# Display_Schematic.net
KiCad netlist of a schematic drawn in Altium Designer
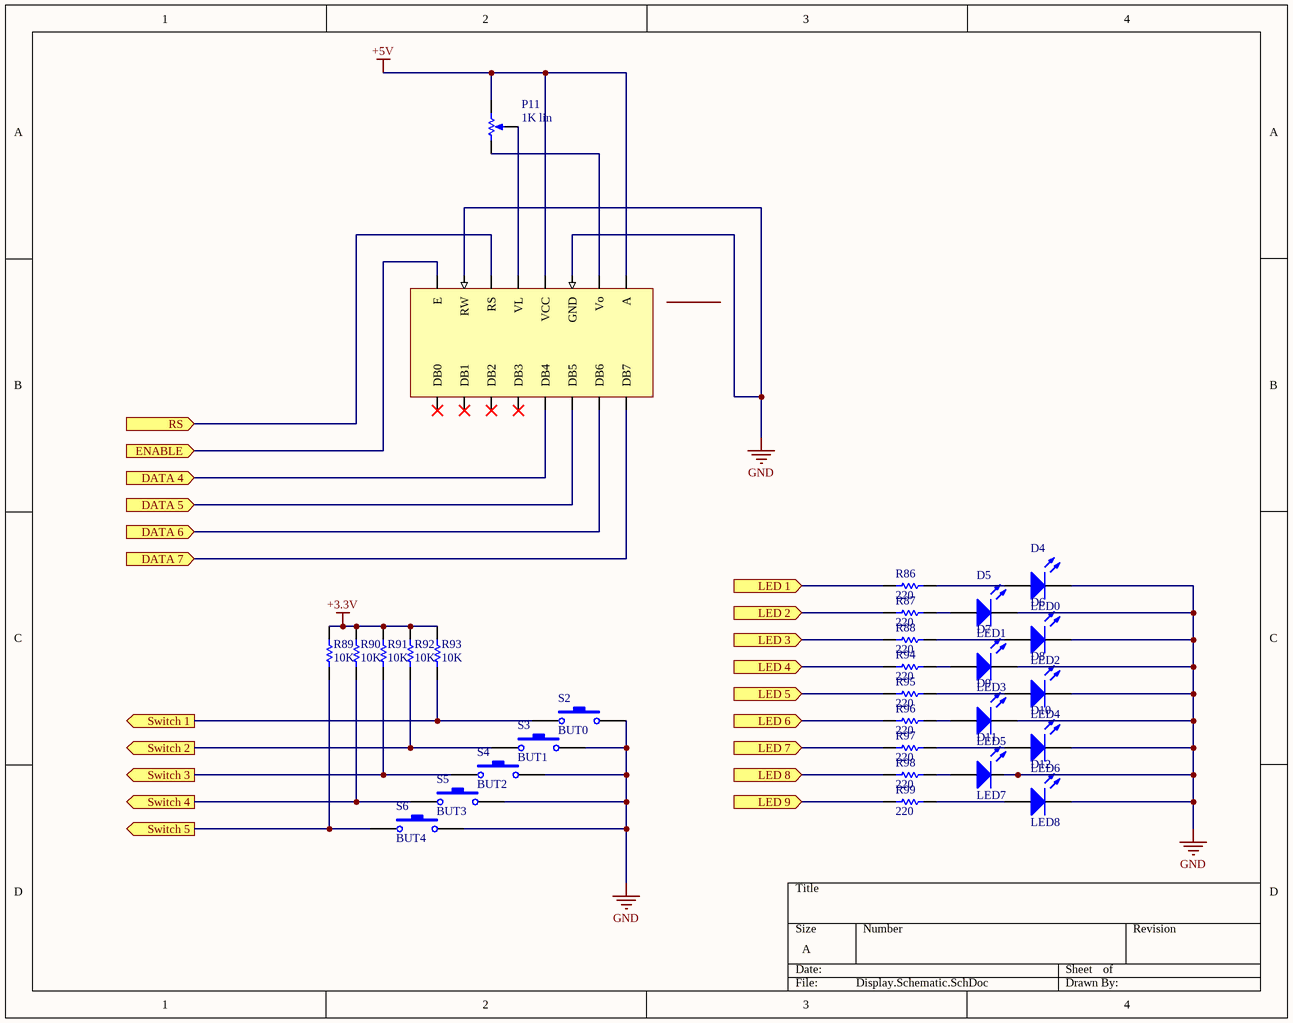
[diagram p0: Display.Schematic.SchDoc]

(export (version "E")
  (design (tool "Eeschema 10.0.6"))
  (components
    (comp (ref "D4")
      (value "LED0")
      (footprint "LED-0")
      (description "Typical INFRARED GaAs LED")
      (fields (field (name "PUBLISHER") "Altium Limited"))
      (libsource (lib "Miscellaneous Devices") (part "LED0"))
    )
    (comp (ref "D5")
      (value "LED1")
      (footprint "LED-0")
      (description "Typical INFRARED GaAs LED")
      (fields (field (name "PUBLISHER") "Altium Limited"))
      (libsource (lib "Miscellaneous Devices") (part "LED0"))
    )
    (comp (ref "D6")
      (value "LED2")
      (footprint "LED-0")
      (description "Typical INFRARED GaAs LED")
      (fields (field (name "PUBLISHER") "Altium Limited"))
      (libsource (lib "Miscellaneous Devices") (part "LED0"))
    )
    (comp (ref "D7")
      (value "LED3")
      (footprint "LED-0")
      (description "Typical INFRARED GaAs LED")
      (fields (field (name "PUBLISHER") "Altium Limited"))
      (libsource (lib "Miscellaneous Devices") (part "LED0"))
    )
    (comp (ref "D8")
      (value "LED4")
      (footprint "LED-0")
      (description "Typical INFRARED GaAs LED")
      (fields (field (name "PUBLISHER") "Altium Limited"))
      (libsource (lib "Miscellaneous Devices") (part "LED0"))
    )
    (comp (ref "D9")
      (value "LED5")
      (footprint "LED-0")
      (description "Typical INFRARED GaAs LED")
      (fields (field (name "PUBLISHER") "Altium Limited"))
      (libsource (lib "Miscellaneous Devices") (part "LED0"))
    )
    (comp (ref "D10")
      (value "LED6")
      (footprint "LED-0")
      (description "Typical INFRARED GaAs LED")
      (fields (field (name "PUBLISHER") "Altium Limited"))
      (libsource (lib "Miscellaneous Devices") (part "LED0"))
    )
    (comp (ref "D11")
      (value "LED7")
      (footprint "LED-0")
      (description "Typical INFRARED GaAs LED")
      (fields (field (name "PUBLISHER") "Altium Limited"))
      (libsource (lib "Miscellaneous Devices") (part "LED0"))
    )
    (comp (ref "D12")
      (value "LED8")
      (footprint "LED-0")
      (description "Typical INFRARED GaAs LED")
      (fields (field (name "PUBLISHER") "Altium Limited"))
      (libsource (lib "Miscellaneous Devices") (part "LED0"))
    )
    (comp (ref "Display")
      (value "16x2 LCD")
      (footprint "Display")
      (libsource (lib "display") (part "Display"))
    )
    (comp (ref "P11")
      (value "1K lin")
      (footprint "VR5")
      (description "Potentiometer")
      (fields (field (name "PUBLISHER") "Altium Limited"))
      (libsource (lib "Miscellaneous Devices") (part "RPot"))
    )
    (comp (ref "R86")
      (value "220")
      (footprint "CAPC1608N")
      (description "Resistor")
      (fields (field (name "PUBLISHER") "Altium Limited"))
      (libsource (lib "Miscellaneous Devices") (part "Res1"))
    )
    (comp (ref "R87")
      (value "220")
      (footprint "CAPC1608N")
      (description "Resistor")
      (fields (field (name "PUBLISHER") "Altium Limited"))
      (libsource (lib "Miscellaneous Devices") (part "Res1"))
    )
    (comp (ref "R88")
      (value "220")
      (footprint "CAPC1608N")
      (description "Resistor")
      (fields (field (name "PUBLISHER") "Altium Limited"))
      (libsource (lib "Miscellaneous Devices") (part "Res1"))
    )
    (comp (ref "R89")
      (value "10K")
      (footprint "CAPC1608N")
      (description "Resistor")
      (fields (field (name "PUBLISHER") "Altium Limited"))
      (libsource (lib "Miscellaneous Devices") (part "Res1"))
    )
    (comp (ref "R90")
      (value "10K")
      (footprint "CAPC1608N")
      (description "Resistor")
      (fields (field (name "PUBLISHER") "Altium Limited"))
      (libsource (lib "Miscellaneous Devices") (part "Res1"))
    )
    (comp (ref "R91")
      (value "10K")
      (footprint "CAPC1608N")
      (description "Resistor")
      (fields (field (name "PUBLISHER") "Altium Limited"))
      (libsource (lib "Miscellaneous Devices") (part "Res1"))
    )
    (comp (ref "R92")
      (value "10K")
      (footprint "CAPC1608N")
      (description "Resistor")
      (fields (field (name "PUBLISHER") "Altium Limited"))
      (libsource (lib "Miscellaneous Devices") (part "Res1"))
    )
    (comp (ref "R93")
      (value "10K")
      (footprint "CAPC1608N")
      (description "Resistor")
      (fields (field (name "PUBLISHER") "Altium Limited"))
      (libsource (lib "Miscellaneous Devices") (part "Res1"))
    )
    (comp (ref "R94")
      (value "220")
      (footprint "CAPC1608N")
      (description "Resistor")
      (fields (field (name "PUBLISHER") "Altium Limited"))
      (libsource (lib "Miscellaneous Devices") (part "Res1"))
    )
    (comp (ref "R95")
      (value "220")
      (footprint "CAPC1608N")
      (description "Resistor")
      (fields (field (name "PUBLISHER") "Altium Limited"))
      (libsource (lib "Miscellaneous Devices") (part "Res1"))
    )
    (comp (ref "R96")
      (value "220")
      (footprint "CAPC1608N")
      (description "Resistor")
      (fields (field (name "PUBLISHER") "Altium Limited"))
      (libsource (lib "Miscellaneous Devices") (part "Res1"))
    )
    (comp (ref "R97")
      (value "220")
      (footprint "CAPC1608N")
      (description "Resistor")
      (fields (field (name "PUBLISHER") "Altium Limited"))
      (libsource (lib "Miscellaneous Devices") (part "Res1"))
    )
    (comp (ref "R98")
      (value "220")
      (footprint "CAPC1608N")
      (description "Resistor")
      (fields (field (name "PUBLISHER") "Altium Limited"))
      (libsource (lib "Miscellaneous Devices") (part "Res1"))
    )
    (comp (ref "R99")
      (value "220")
      (footprint "CAPC1608N")
      (description "Resistor")
      (fields (field (name "PUBLISHER") "Altium Limited"))
      (libsource (lib "Miscellaneous Devices") (part "Res1"))
    )
    (comp (ref "S2")
      (value "BUT0")
      (footprint "SPST-2")
      (description "Switch")
      (fields (field (name "PUBLISHER") "Altium Limited"))
      (libsource (lib "Miscellaneous Devices") (part "SW-PB"))
    )
    (comp (ref "S3")
      (value "BUT1")
      (footprint "SPST-2")
      (description "Switch")
      (fields (field (name "PUBLISHER") "Altium Limited"))
      (libsource (lib "Miscellaneous Devices") (part "SW-PB"))
    )
    (comp (ref "S4")
      (value "BUT2")
      (footprint "SPST-2")
      (description "Switch")
      (fields (field (name "PUBLISHER") "Altium Limited"))
      (libsource (lib "Miscellaneous Devices") (part "SW-PB"))
    )
    (comp (ref "S5")
      (value "BUT3")
      (footprint "SPST-2")
      (description "Switch")
      (fields (field (name "PUBLISHER") "Altium Limited"))
      (libsource (lib "Miscellaneous Devices") (part "SW-PB"))
    )
    (comp (ref "S6")
      (value "BUT4")
      (footprint "SPST-2")
      (description "Switch")
      (fields (field (name "PUBLISHER") "Altium Limited"))
      (libsource (lib "Miscellaneous Devices") (part "SW-PB"))
    )
  )
  (nets
    (net (code "1") (name "+3.3V") (class "Default")
      (node (ref "R89") (pin "2") (pinfunction "2_2") (pintype "passive"))
      (node (ref "R90") (pin "2") (pinfunction "2_2") (pintype "passive"))
      (node (ref "R91") (pin "2") (pinfunction "2_2") (pintype "passive"))
      (node (ref "R92") (pin "2") (pinfunction "2_2") (pintype "passive"))
      (node (ref "R93") (pin "2") (pinfunction "2_2") (pintype "passive"))
    )
    (net (code "2") (name "+5V") (class "Default")
      (node (ref "Display") (pin "16") (pinfunction "A_16") (pintype "passive"))
      (node (ref "Display") (pin "2") (pinfunction "VCC_2") (pintype "passive"))
      (node (ref "P11") (pin "2") (pinfunction "BOT_2") (pintype "passive"))
    )
    (net (code "3") (name "/DATA 4") (class "Default")
      (node (ref "Display") (pin "10") (pinfunction "DB4_10") (pintype "passive"))
    )
    (net (code "4") (name "/DATA 5") (class "Default")
      (node (ref "Display") (pin "9") (pinfunction "DB5_9") (pintype "passive"))
    )
    (net (code "5") (name "/DATA 6") (class "Default")
      (node (ref "Display") (pin "8") (pinfunction "DB6_8") (pintype "passive"))
    )
    (net (code "6") (name "/DATA 7") (class "Default")
      (node (ref "Display") (pin "7") (pinfunction "DB7_7") (pintype "passive"))
    )
    (net (code "7") (name "/ENABLE") (class "Default")
      (node (ref "Display") (pin "6") (pinfunction "E_6") (pintype "passive"))
    )
    (net (code "8") (name "/LED 1") (class "Default")
      (node (ref "R86") (pin "1") (pinfunction "1_1") (pintype "passive"))
    )
    (net (code "9") (name "/LED 2") (class "Default")
      (node (ref "R87") (pin "1") (pinfunction "1_1") (pintype "passive"))
    )
    (net (code "10") (name "/LED 3") (class "Default")
      (node (ref "R88") (pin "1") (pinfunction "1_1") (pintype "passive"))
    )
    (net (code "11") (name "/LED 4") (class "Default")
      (node (ref "R94") (pin "1") (pinfunction "1_1") (pintype "passive"))
    )
    (net (code "12") (name "/LED 5") (class "Default")
      (node (ref "R95") (pin "1") (pinfunction "1_1") (pintype "passive"))
    )
    (net (code "13") (name "/LED 6") (class "Default")
      (node (ref "R96") (pin "1") (pinfunction "1_1") (pintype "passive"))
    )
    (net (code "14") (name "/LED 7") (class "Default")
      (node (ref "R97") (pin "1") (pinfunction "1_1") (pintype "passive"))
    )
    (net (code "15") (name "/LED 8") (class "Default")
      (node (ref "R98") (pin "1") (pinfunction "1_1") (pintype "passive"))
    )
    (net (code "16") (name "/LED 9") (class "Default")
      (node (ref "R99") (pin "1") (pinfunction "1_1") (pintype "passive"))
    )
    (net (code "17") (name "/RS") (class "Default")
      (node (ref "Display") (pin "4") (pinfunction "RS_4") (pintype "passive"))
    )
    (net (code "18") (name "/Switch 1") (class "Default")
      (node (ref "R93") (pin "1") (pinfunction "1_1") (pintype "passive"))
      (node (ref "S2") (pin "1") (pinfunction "1_1") (pintype "passive"))
    )
    (net (code "19") (name "/Switch 2") (class "Default")
      (node (ref "R92") (pin "1") (pinfunction "1_1") (pintype "passive"))
      (node (ref "S3") (pin "1") (pinfunction "1_1") (pintype "passive"))
    )
    (net (code "20") (name "/Switch 3") (class "Default")
      (node (ref "R91") (pin "1") (pinfunction "1_1") (pintype "passive"))
      (node (ref "S4") (pin "1") (pinfunction "1_1") (pintype "passive"))
    )
    (net (code "21") (name "/Switch 4") (class "Default")
      (node (ref "R90") (pin "1") (pinfunction "1_1") (pintype "passive"))
      (node (ref "S5") (pin "1") (pinfunction "1_1") (pintype "passive"))
    )
    (net (code "22") (name "/Switch 5") (class "Default")
      (node (ref "R89") (pin "1") (pinfunction "1_1") (pintype "passive"))
      (node (ref "S6") (pin "1") (pinfunction "1_1") (pintype "passive"))
    )
    (net (code "23") (name "GND") (class "Default")
      (node (ref "D10") (pin "2") (pinfunction "K_2") (pintype "passive"))
      (node (ref "D11") (pin "2") (pinfunction "K_2") (pintype "passive"))
      (node (ref "D12") (pin "2") (pinfunction "K_2") (pintype "passive"))
      (node (ref "D4") (pin "2") (pinfunction "K_2") (pintype "passive"))
      (node (ref "D5") (pin "2") (pinfunction "K_2") (pintype "passive"))
      (node (ref "D6") (pin "2") (pinfunction "K_2") (pintype "passive"))
      (node (ref "D7") (pin "2") (pinfunction "K_2") (pintype "passive"))
      (node (ref "D8") (pin "2") (pinfunction "K_2") (pintype "passive"))
      (node (ref "D9") (pin "2") (pinfunction "K_2") (pintype "passive"))
      (node (ref "Display") (pin "1") (pinfunction "GND_1") (pintype "input"))
      (node (ref "Display") (pin "5") (pinfunction "RW_5") (pintype "input"))
      (node (ref "S2") (pin "2") (pinfunction "2_2") (pintype "passive"))
      (node (ref "S3") (pin "2") (pinfunction "2_2") (pintype "passive"))
      (node (ref "S4") (pin "2") (pinfunction "2_2") (pintype "passive"))
      (node (ref "S5") (pin "2") (pinfunction "2_2") (pintype "passive"))
      (node (ref "S6") (pin "2") (pinfunction "2_2") (pintype "passive"))
    )
    (net (code "24") (name "Net-(D4-A)") (class "Default")
      (node (ref "D4") (pin "1") (pinfunction "A_1") (pintype "passive"))
      (node (ref "R86") (pin "2") (pinfunction "2_2") (pintype "passive"))
    )
    (net (code "25") (name "Net-(D5-A)") (class "Default")
      (node (ref "D5") (pin "1") (pinfunction "A_1") (pintype "passive"))
      (node (ref "R87") (pin "2") (pinfunction "2_2") (pintype "passive"))
    )
    (net (code "26") (name "Net-(D6-A)") (class "Default")
      (node (ref "D6") (pin "1") (pinfunction "A_1") (pintype "passive"))
      (node (ref "R88") (pin "2") (pinfunction "2_2") (pintype "passive"))
    )
    (net (code "27") (name "Net-(D7-A)") (class "Default")
      (node (ref "D7") (pin "1") (pinfunction "A_1") (pintype "passive"))
      (node (ref "R94") (pin "2") (pinfunction "2_2") (pintype "passive"))
    )
    (net (code "28") (name "Net-(D8-A)") (class "Default")
      (node (ref "D8") (pin "1") (pinfunction "A_1") (pintype "passive"))
      (node (ref "R95") (pin "2") (pinfunction "2_2") (pintype "passive"))
    )
    (net (code "29") (name "Net-(D9-A)") (class "Default")
      (node (ref "D9") (pin "1") (pinfunction "A_1") (pintype "passive"))
      (node (ref "R96") (pin "2") (pinfunction "2_2") (pintype "passive"))
    )
    (net (code "30") (name "Net-(D10-A)") (class "Default")
      (node (ref "D10") (pin "1") (pinfunction "A_1") (pintype "passive"))
      (node (ref "R97") (pin "2") (pinfunction "2_2") (pintype "passive"))
    )
    (net (code "31") (name "Net-(D11-A)") (class "Default")
      (node (ref "D11") (pin "1") (pinfunction "A_1") (pintype "passive"))
      (node (ref "R98") (pin "2") (pinfunction "2_2") (pintype "passive"))
    )
    (net (code "32") (name "Net-(D12-A)") (class "Default")
      (node (ref "D12") (pin "1") (pinfunction "A_1") (pintype "passive"))
      (node (ref "R99") (pin "2") (pinfunction "2_2") (pintype "passive"))
    )
    (net (code "33") (name "Net-(Display-VL)") (class "Default")
      (node (ref "Display") (pin "3") (pinfunction "VL_3") (pintype "passive"))
      (node (ref "P11") (pin "3") (pinfunction "TAP_3") (pintype "passive"))
    )
    (net (code "34") (name "Net-(Display-Vo)") (class "Default")
      (node (ref "Display") (pin "15") (pinfunction "Vo_15") (pintype "passive"))
      (node (ref "P11") (pin "1") (pinfunction "TOP_1") (pintype "passive"))
    )
    (net (code "35") (name "unconnected-(Display-DB0-Pad14)") (class "Default")
      (node (ref "Display") (pin "14") (pinfunction "DB0_14") (pintype "passive+no_connect"))
    )
    (net (code "36") (name "unconnected-(Display-DB1-Pad13)") (class "Default")
      (node (ref "Display") (pin "13") (pinfunction "DB1_13") (pintype "passive+no_connect"))
    )
    (net (code "37") (name "unconnected-(Display-DB2-Pad12)") (class "Default")
      (node (ref "Display") (pin "12") (pinfunction "DB2_12") (pintype "passive+no_connect"))
    )
    (net (code "38") (name "unconnected-(Display-DB3-Pad11)") (class "Default")
      (node (ref "Display") (pin "11") (pinfunction "DB3_11") (pintype "passive+no_connect"))
    )
  )
)
